# I2C-7313-cTc.net
KiCad netlist of a schematic drawn in EAGLE
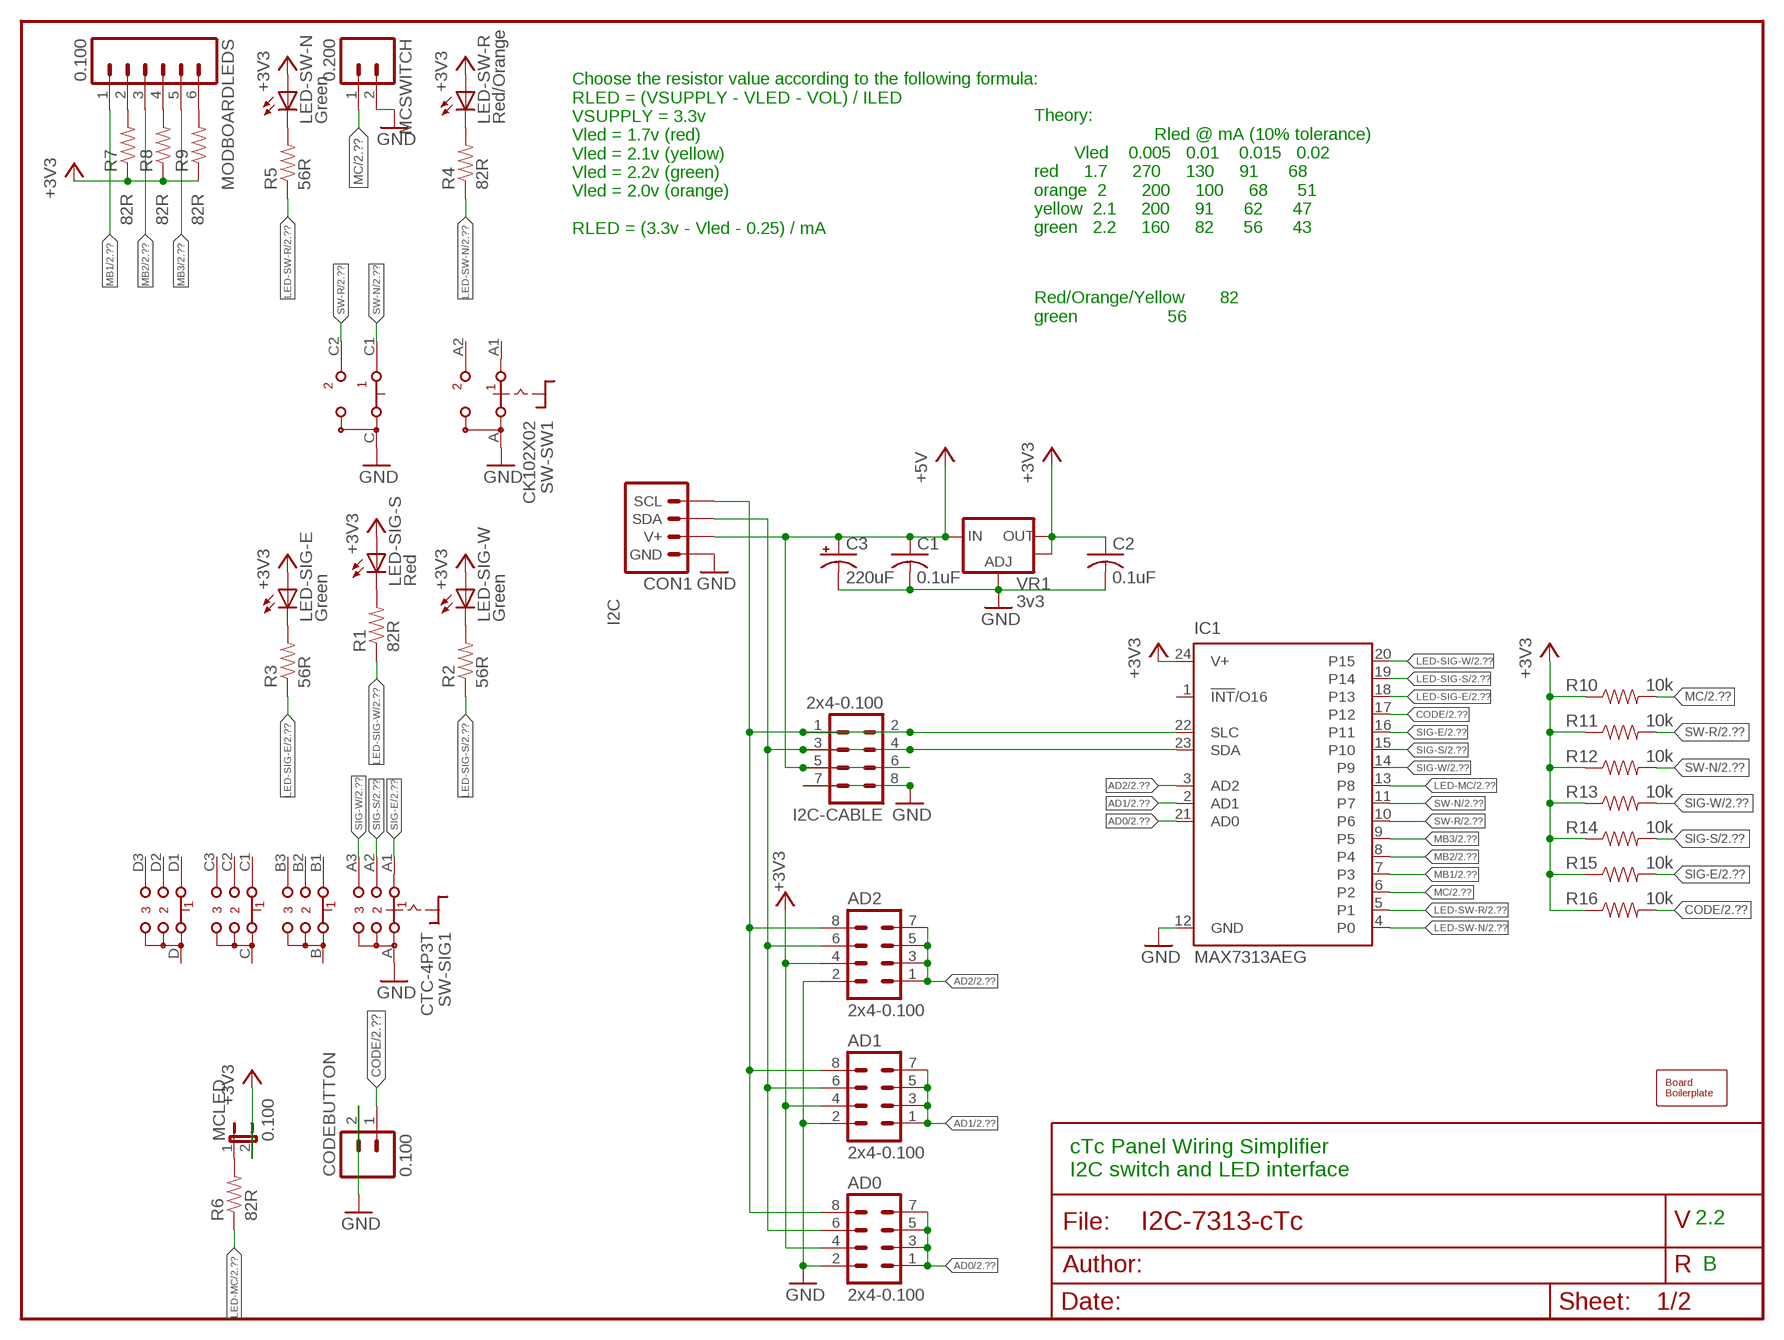
[diagram p0: schematic, sheet 1]
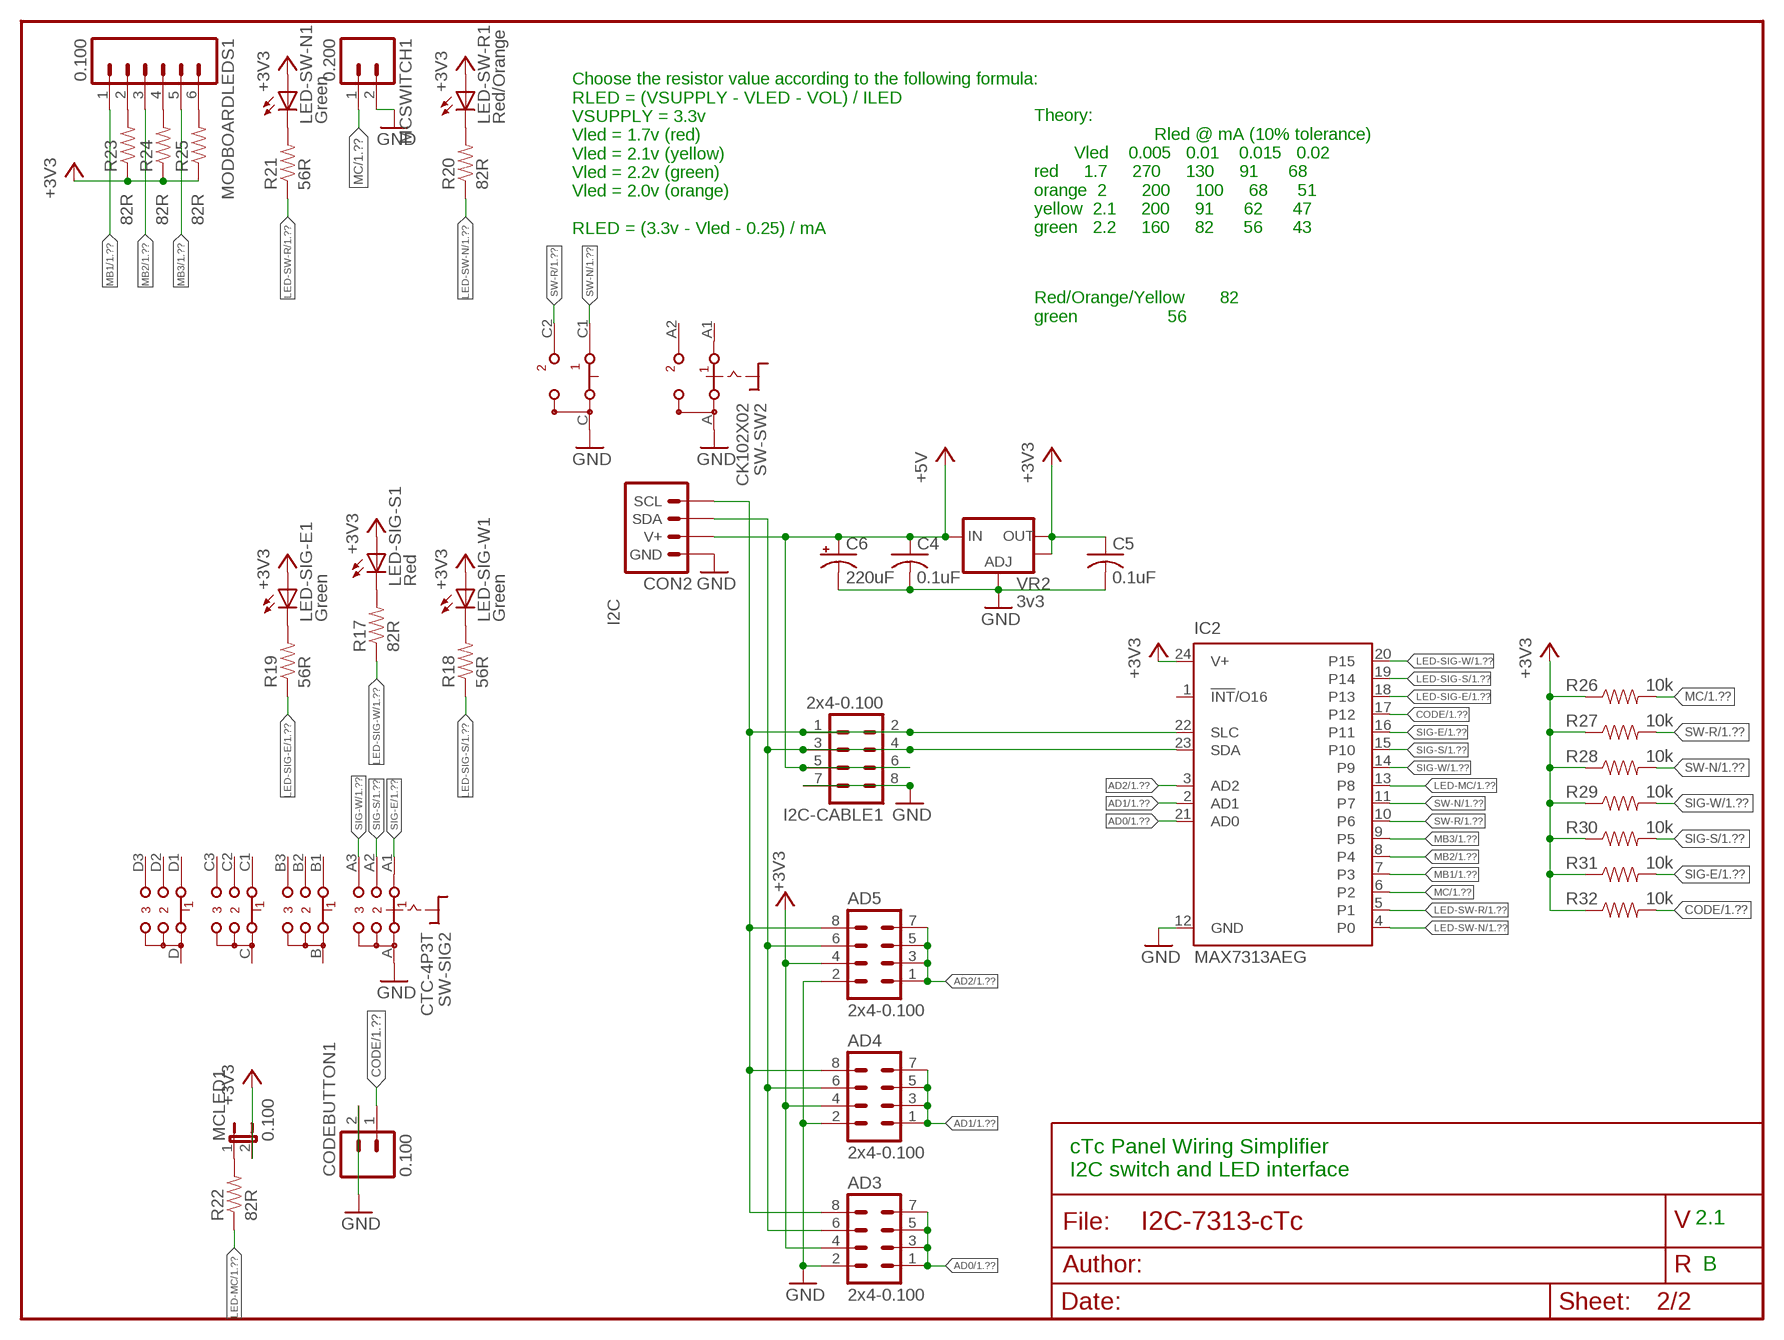
[diagram p1: schematic, sheet 2]

(export (version "E")
  (design (tool "Eeschema 10.0.6"))
  (components
    (comp (ref "AD3")
      (value "2x4-0.100")
      (footprint "eagle-import:MA04-2")
      (libsource (lib "eagle-import") (part "MA04-2"))
    )
    (comp (ref "AD4")
      (value "2x4-0.100")
      (footprint "eagle-import:MA04-2")
      (libsource (lib "eagle-import") (part "MA04-2"))
    )
    (comp (ref "AD5")
      (value "2x4-0.100")
      (footprint "eagle-import:MA04-2")
      (libsource (lib "eagle-import") (part "MA04-2"))
    )
    (comp (ref "C4")
      (value "0.1uF")
      (footprint "eagle-import:0603-CAP")
      (libsource (lib "eagle-import") (part "CAP0603"))
    )
    (comp (ref "C5")
      (value "0.1uF")
      (footprint "eagle-import:0603-CAP")
      (libsource (lib "eagle-import") (part "CAP0603"))
    )
    (comp (ref "C6")
      (value "220uF")
      (footprint "eagle-import:0810-CAP")
      (libsource (lib "eagle-import") (part "CAP-POL0810"))
    )
    (comp (ref "CODEBUTTON1")
      (value "0.100")
      (footprint "eagle-import:1X02_LOCK")
      (libsource (lib "eagle-import") (part "CONNECTOR-M021X02-LOCK"))
    )
    (comp (ref "CON2")
      (value "I2C")
      (footprint "eagle-import:I2C-L")
      (libsource (lib "eagle-import") (part "CONNECTOR-I2CLEFT"))
    )
    (comp (ref "I2C-CABLE1")
      (value "2x4-0.100")
      (footprint "eagle-import:MA04-2")
      (libsource (lib "eagle-import") (part "MA04-2"))
    )
    (comp (ref "IC2")
      (value "MAX7313AEG")
      (footprint "eagle-import:QSOP24")
      (fields (field (name "MPN") "MAX7313AEG+"))
      (libsource (lib "eagle-import") (part "MAX7313AEG"))
    )
    (comp (ref "LED-SIG-E1")
      (value "Green")
      (footprint "eagle-import:LED3MM")
      (libsource (lib "eagle-import") (part "LEDLED3MM"))
    )
    (comp (ref "LED-SIG-S1")
      (value "Red")
      (footprint "eagle-import:LED3MM")
      (libsource (lib "eagle-import") (part "LEDLED3MM"))
    )
    (comp (ref "LED-SIG-W1")
      (value "Green")
      (footprint "eagle-import:LED3MM")
      (libsource (lib "eagle-import") (part "LEDLED3MM"))
    )
    (comp (ref "LED-SW-N1")
      (value "Green")
      (footprint "eagle-import:LED3MM")
      (libsource (lib "eagle-import") (part "LEDLED3MM"))
    )
    (comp (ref "LED-SW-R1")
      (value "Red/Orange")
      (footprint "eagle-import:LED3MM")
      (libsource (lib "eagle-import") (part "LEDLED3MM"))
    )
    (comp (ref "MCLED1")
      (value "0.100")
      (footprint "eagle-import:1X02_LOCK")
      (libsource (lib "eagle-import") (part "JUMPER-2PTH_LOCK"))
    )
    (comp (ref "MCSWITCH1")
      (value "0.200")
      (footprint "eagle-import:SCREWTERMINAL-5MM-2")
      (libsource (lib "eagle-import") (part "CONNECTOR-M025MM-LOCK"))
    )
    (comp (ref "MODBOARDLEDS1")
      (value "0.100")
      (footprint "eagle-import:1X06_LOCK_LONGPADS")
      (libsource (lib "eagle-import") (part "CONNECTOR-M06LOCK_LONGPADS"))
    )
    (comp (ref "R17")
      (value "82R")
      (footprint "eagle-import:0603-RES")
      (libsource (lib "eagle-import") (part "R0603-RES"))
    )
    (comp (ref "R18")
      (value "56R")
      (footprint "eagle-import:0603-RES")
      (libsource (lib "eagle-import") (part "R0603-RES"))
    )
    (comp (ref "R19")
      (value "56R")
      (footprint "eagle-import:0603-RES")
      (libsource (lib "eagle-import") (part "R0603-RES"))
    )
    (comp (ref "R20")
      (value "82R")
      (footprint "eagle-import:0603-RES")
      (libsource (lib "eagle-import") (part "R0603-RES"))
    )
    (comp (ref "R21")
      (value "56R")
      (footprint "eagle-import:0603-RES")
      (libsource (lib "eagle-import") (part "R0603-RES"))
    )
    (comp (ref "R22")
      (value "82R")
      (footprint "eagle-import:0603-RES")
      (libsource (lib "eagle-import") (part "R0603-RES"))
    )
    (comp (ref "R23")
      (value "82R")
      (footprint "eagle-import:0603-RES")
      (libsource (lib "eagle-import") (part "R0603-RES"))
    )
    (comp (ref "R24")
      (value "82R")
      (footprint "eagle-import:0603-RES")
      (libsource (lib "eagle-import") (part "R0603-RES"))
    )
    (comp (ref "R25")
      (value "82R")
      (footprint "eagle-import:0603-RES")
      (libsource (lib "eagle-import") (part "R0603-RES"))
    )
    (comp (ref "R26")
      (value "10k")
      (footprint "eagle-import:0603-RES")
      (libsource (lib "eagle-import") (part "R0603-RES"))
    )
    (comp (ref "R27")
      (value "10k")
      (footprint "eagle-import:0603-RES")
      (libsource (lib "eagle-import") (part "R0603-RES"))
    )
    (comp (ref "R28")
      (value "10k")
      (footprint "eagle-import:0603-RES")
      (libsource (lib "eagle-import") (part "R0603-RES"))
    )
    (comp (ref "R29")
      (value "10k")
      (footprint "eagle-import:0603-RES")
      (libsource (lib "eagle-import") (part "R0603-RES"))
    )
    (comp (ref "R30")
      (value "10k")
      (footprint "eagle-import:0603-RES")
      (libsource (lib "eagle-import") (part "R0603-RES"))
    )
    (comp (ref "R31")
      (value "10k")
      (footprint "eagle-import:0603-RES")
      (libsource (lib "eagle-import") (part "R0603-RES"))
    )
    (comp (ref "R32")
      (value "10k")
      (footprint "eagle-import:0603-RES")
      (libsource (lib "eagle-import") (part "R0603-RES"))
    )
    (comp (ref "SW-SIG2")
      (value "CTC-4P3T")
      (footprint "eagle-import:CTC-4P3T")
      (libsource (lib "eagle-import") (part "CTC-4P3T"))
    )
    (comp (ref "SW-SW2")
      (value "CK102X02")
      (footprint "eagle-import:CK102X02")
      (libsource (lib "eagle-import") (part "CK102X02"))
    )
    (comp (ref "VR2")
      (value "3v3")
      (footprint "eagle-import:SOT223")
      (libsource (lib "eagle-import") (part "VREG_LM1117SOT223"))
    )
    (comp (ref "AD0")
      (value "2x4-0.100")
      (footprint "eagle-import:MA04-2")
      (libsource (lib "eagle-import") (part "MA04-2"))
    )
    (comp (ref "AD1")
      (value "2x4-0.100")
      (footprint "eagle-import:MA04-2")
      (libsource (lib "eagle-import") (part "MA04-2"))
    )
    (comp (ref "AD2")
      (value "2x4-0.100")
      (footprint "eagle-import:MA04-2")
      (libsource (lib "eagle-import") (part "MA04-2"))
    )
    (comp (ref "BOARD1")
      (value "BOARD")
      (footprint "eagle-import:BOARD-SEEED10X15_2-NOHOLES")
      (libsource (lib "eagle-import") (part "BOARD100X150X2-NOHOLES"))
    )
    (comp (ref "C1")
      (value "0.1uF")
      (footprint "eagle-import:0603-CAP")
      (libsource (lib "eagle-import") (part "CAP0603"))
    )
    (comp (ref "C2")
      (value "0.1uF")
      (footprint "eagle-import:0603-CAP")
      (libsource (lib "eagle-import") (part "CAP0603"))
    )
    (comp (ref "C3")
      (value "220uF")
      (footprint "eagle-import:0810-CAP")
      (libsource (lib "eagle-import") (part "CAP-POL0810"))
    )
    (comp (ref "CODEBUTTON")
      (value "0.100")
      (footprint "eagle-import:1X02_LOCK")
      (libsource (lib "eagle-import") (part "CONNECTOR-M021X02-LOCK"))
    )
    (comp (ref "CON1")
      (value "I2C")
      (footprint "eagle-import:I2C-L")
      (libsource (lib "eagle-import") (part "CONNECTOR-I2CLEFT"))
    )
    (comp (ref "I2C-CABLE")
      (value "2x4-0.100")
      (footprint "eagle-import:MA04-2")
      (libsource (lib "eagle-import") (part "MA04-2"))
    )
    (comp (ref "IC1")
      (value "MAX7313AEG")
      (footprint "eagle-import:QSOP24")
      (fields (field (name "MPN") "MAX7313AEG+"))
      (libsource (lib "eagle-import") (part "MAX7313AEG"))
    )
    (comp (ref "LED-SIG-E")
      (value "Green")
      (footprint "eagle-import:LED3MM")
      (libsource (lib "eagle-import") (part "LEDLED3MM"))
    )
    (comp (ref "LED-SIG-S")
      (value "Red")
      (footprint "eagle-import:LED3MM")
      (libsource (lib "eagle-import") (part "LEDLED3MM"))
    )
    (comp (ref "LED-SIG-W")
      (value "Green")
      (footprint "eagle-import:LED3MM")
      (libsource (lib "eagle-import") (part "LEDLED3MM"))
    )
    (comp (ref "LED-SW-N")
      (value "Green")
      (footprint "eagle-import:LED3MM")
      (libsource (lib "eagle-import") (part "LEDLED3MM"))
    )
    (comp (ref "LED-SW-R")
      (value "Red/Orange")
      (footprint "eagle-import:LED3MM")
      (libsource (lib "eagle-import") (part "LEDLED3MM"))
    )
    (comp (ref "MCLED")
      (value "0.100")
      (footprint "eagle-import:1X02_LOCK")
      (libsource (lib "eagle-import") (part "JUMPER-2PTH_LOCK"))
    )
    (comp (ref "MCSWITCH")
      (value "0.200")
      (footprint "eagle-import:SCREWTERMINAL-5MM-2")
      (libsource (lib "eagle-import") (part "CONNECTOR-M025MM-LOCK"))
    )
    (comp (ref "MODBOARDLEDS")
      (value "0.100")
      (footprint "eagle-import:1X06_LOCK_LONGPADS")
      (libsource (lib "eagle-import") (part "CONNECTOR-M06LOCK_LONGPADS"))
    )
    (comp (ref "R1")
      (value "82R")
      (footprint "eagle-import:0603-RES")
      (libsource (lib "eagle-import") (part "R0603-RES"))
    )
    (comp (ref "R2")
      (value "56R")
      (footprint "eagle-import:0603-RES")
      (libsource (lib "eagle-import") (part "R0603-RES"))
    )
    (comp (ref "R3")
      (value "56R")
      (footprint "eagle-import:0603-RES")
      (libsource (lib "eagle-import") (part "R0603-RES"))
    )
    (comp (ref "R4")
      (value "82R")
      (footprint "eagle-import:0603-RES")
      (libsource (lib "eagle-import") (part "R0603-RES"))
    )
    (comp (ref "R5")
      (value "56R")
      (footprint "eagle-import:0603-RES")
      (libsource (lib "eagle-import") (part "R0603-RES"))
    )
    (comp (ref "R6")
      (value "82R")
      (footprint "eagle-import:0603-RES")
      (libsource (lib "eagle-import") (part "R0603-RES"))
    )
    (comp (ref "R7")
      (value "82R")
      (footprint "eagle-import:0603-RES")
      (libsource (lib "eagle-import") (part "R0603-RES"))
    )
    (comp (ref "R8")
      (value "82R")
      (footprint "eagle-import:0603-RES")
      (libsource (lib "eagle-import") (part "R0603-RES"))
    )
    (comp (ref "R9")
      (value "82R")
      (footprint "eagle-import:0603-RES")
      (libsource (lib "eagle-import") (part "R0603-RES"))
    )
    (comp (ref "R10")
      (value "10k")
      (footprint "eagle-import:0603-RES")
      (libsource (lib "eagle-import") (part "R0603-RES"))
    )
    (comp (ref "R11")
      (value "10k")
      (footprint "eagle-import:0603-RES")
      (libsource (lib "eagle-import") (part "R0603-RES"))
    )
    (comp (ref "R12")
      (value "10k")
      (footprint "eagle-import:0603-RES")
      (libsource (lib "eagle-import") (part "R0603-RES"))
    )
    (comp (ref "R13")
      (value "10k")
      (footprint "eagle-import:0603-RES")
      (libsource (lib "eagle-import") (part "R0603-RES"))
    )
    (comp (ref "R14")
      (value "10k")
      (footprint "eagle-import:0603-RES")
      (libsource (lib "eagle-import") (part "R0603-RES"))
    )
    (comp (ref "R15")
      (value "10k")
      (footprint "eagle-import:0603-RES")
      (libsource (lib "eagle-import") (part "R0603-RES"))
    )
    (comp (ref "R16")
      (value "10k")
      (footprint "eagle-import:0603-RES")
      (libsource (lib "eagle-import") (part "R0603-RES"))
    )
    (comp (ref "SW-SIG1")
      (value "CTC-4P3T")
      (footprint "eagle-import:CTC-4P3T")
      (libsource (lib "eagle-import") (part "CTC-4P3T"))
    )
    (comp (ref "SW-SW1")
      (value "CK102X02")
      (footprint "eagle-import:CK102X02")
      (libsource (lib "eagle-import") (part "CK102X02"))
    )
    (comp (ref "VR1")
      (value "3v3")
      (footprint "eagle-import:SOT223")
      (libsource (lib "eagle-import") (part "VREG_LM1117SOT223"))
    )
  )
  (nets
    (net (code "1") (name "+3V3") (class "Default")
      (node (ref "AD0") (pin "4") (pinfunction "4_4") (pintype "passive"))
      (node (ref "AD1") (pin "4") (pinfunction "4_4") (pintype "passive"))
      (node (ref "AD2") (pin "4") (pinfunction "4_4") (pintype "passive"))
      (node (ref "AD3") (pin "4") (pinfunction "4_4") (pintype "passive"))
      (node (ref "AD4") (pin "4") (pinfunction "4_4") (pintype "passive"))
      (node (ref "AD5") (pin "4") (pinfunction "4_4") (pintype "passive"))
      (node (ref "C2") (pin "1") (pinfunction "1_1") (pintype "passive"))
      (node (ref "C5") (pin "1") (pinfunction "1_1") (pintype "passive"))
      (node (ref "IC1") (pin "24") (pinfunction "V+_24") (pintype "power_in"))
      (node (ref "IC2") (pin "24") (pinfunction "V+_24") (pintype "power_in"))
      (node (ref "LED-SIG-E") (pin "A") (pinfunction "A_A") (pintype "passive"))
      (node (ref "LED-SIG-E1") (pin "A") (pinfunction "A_A") (pintype "passive"))
      (node (ref "LED-SIG-S") (pin "A") (pinfunction "A_A") (pintype "passive"))
      (node (ref "LED-SIG-S1") (pin "A") (pinfunction "A_A") (pintype "passive"))
      (node (ref "LED-SIG-W") (pin "A") (pinfunction "A_A") (pintype "passive"))
      (node (ref "LED-SIG-W1") (pin "A") (pinfunction "A_A") (pintype "passive"))
      (node (ref "LED-SW-N") (pin "A") (pinfunction "A_A") (pintype "passive"))
      (node (ref "LED-SW-N1") (pin "A") (pinfunction "A_A") (pintype "passive"))
      (node (ref "LED-SW-R") (pin "A") (pinfunction "A_A") (pintype "passive"))
      (node (ref "LED-SW-R1") (pin "A") (pinfunction "A_A") (pintype "passive"))
      (node (ref "MCLED") (pin "2") (pinfunction "2_2") (pintype "passive"))
      (node (ref "MCLED1") (pin "2") (pinfunction "2_2") (pintype "passive"))
      (node (ref "R10") (pin "1") (pinfunction "1_1") (pintype "passive"))
      (node (ref "R11") (pin "1") (pinfunction "1_1") (pintype "passive"))
      (node (ref "R12") (pin "1") (pinfunction "1_1") (pintype "passive"))
      (node (ref "R13") (pin "1") (pinfunction "1_1") (pintype "passive"))
      (node (ref "R14") (pin "1") (pinfunction "1_1") (pintype "passive"))
      (node (ref "R15") (pin "1") (pinfunction "1_1") (pintype "passive"))
      (node (ref "R16") (pin "1") (pinfunction "1_1") (pintype "passive"))
      (node (ref "R23") (pin "1") (pinfunction "1_1") (pintype "passive"))
      (node (ref "R24") (pin "1") (pinfunction "1_1") (pintype "passive"))
      (node (ref "R25") (pin "1") (pinfunction "1_1") (pintype "passive"))
      (node (ref "R26") (pin "1") (pinfunction "1_1") (pintype "passive"))
      (node (ref "R27") (pin "1") (pinfunction "1_1") (pintype "passive"))
      (node (ref "R28") (pin "1") (pinfunction "1_1") (pintype "passive"))
      (node (ref "R29") (pin "1") (pinfunction "1_1") (pintype "passive"))
      (node (ref "R30") (pin "1") (pinfunction "1_1") (pintype "passive"))
      (node (ref "R31") (pin "1") (pinfunction "1_1") (pintype "passive"))
      (node (ref "R32") (pin "1") (pinfunction "1_1") (pintype "passive"))
      (node (ref "R7") (pin "1") (pinfunction "1_1") (pintype "passive"))
      (node (ref "R8") (pin "1") (pinfunction "1_1") (pintype "passive"))
      (node (ref "R9") (pin "1") (pinfunction "1_1") (pintype "passive"))
      (node (ref "VR1") (pin "2") (pinfunction "OUT_2") (pintype "power_in"))
      (node (ref "VR1") (pin "4") (pinfunction "OUT_4") (pintype "power_in"))
      (node (ref "VR2") (pin "2") (pinfunction "OUT_2") (pintype "power_in"))
      (node (ref "VR2") (pin "4") (pinfunction "OUT_4") (pintype "power_in"))
    )
    (net (code "2") (name "+5V") (class "Default")
      (node (ref "C1") (pin "1") (pinfunction "1_1") (pintype "passive"))
      (node (ref "C3") (pin "+") (pinfunction "+_+") (pintype "passive"))
      (node (ref "C4") (pin "1") (pinfunction "1_1") (pintype "passive"))
      (node (ref "C6") (pin "+") (pinfunction "+_+") (pintype "passive"))
      (node (ref "CON1") (pin "V+") (pinfunction "V+_V+") (pintype "passive"))
      (node (ref "CON1") (pin "V+@1") (pinfunction "V+_V+@1") (pintype "passive"))
      (node (ref "CON2") (pin "V+") (pinfunction "V+_V+") (pintype "passive"))
      (node (ref "CON2") (pin "V+@1") (pinfunction "V+_V+@1") (pintype "passive"))
      (node (ref "I2C-CABLE") (pin "5") (pinfunction "5_5") (pintype "passive"))
      (node (ref "I2C-CABLE") (pin "6") (pinfunction "6_6") (pintype "passive"))
      (node (ref "I2C-CABLE1") (pin "5") (pinfunction "5_5") (pintype "passive"))
      (node (ref "I2C-CABLE1") (pin "6") (pinfunction "6_6") (pintype "passive"))
      (node (ref "VR1") (pin "3") (pinfunction "IN_3") (pintype "input"))
      (node (ref "VR2") (pin "3") (pinfunction "IN_3") (pintype "input"))
    )
    (net (code "3") (name "AD0") (class "Default")
      (node (ref "AD0") (pin "1") (pinfunction "1_1") (pintype "passive"))
      (node (ref "AD0") (pin "3") (pinfunction "3_3") (pintype "passive"))
      (node (ref "AD0") (pin "5") (pinfunction "5_5") (pintype "passive"))
      (node (ref "AD0") (pin "7") (pinfunction "7_7") (pintype "passive"))
      (node (ref "AD3") (pin "1") (pinfunction "1_1") (pintype "passive"))
      (node (ref "AD3") (pin "3") (pinfunction "3_3") (pintype "passive"))
      (node (ref "AD3") (pin "5") (pinfunction "5_5") (pintype "passive"))
      (node (ref "AD3") (pin "7") (pinfunction "7_7") (pintype "passive"))
      (node (ref "IC1") (pin "21") (pinfunction "AD0_21") (pintype "input"))
      (node (ref "IC2") (pin "21") (pinfunction "AD0_21") (pintype "input"))
    )
    (net (code "4") (name "AD1") (class "Default")
      (node (ref "AD1") (pin "1") (pinfunction "1_1") (pintype "passive"))
      (node (ref "AD1") (pin "3") (pinfunction "3_3") (pintype "passive"))
      (node (ref "AD1") (pin "5") (pinfunction "5_5") (pintype "passive"))
      (node (ref "AD1") (pin "7") (pinfunction "7_7") (pintype "passive"))
      (node (ref "AD4") (pin "1") (pinfunction "1_1") (pintype "passive"))
      (node (ref "AD4") (pin "3") (pinfunction "3_3") (pintype "passive"))
      (node (ref "AD4") (pin "5") (pinfunction "5_5") (pintype "passive"))
      (node (ref "AD4") (pin "7") (pinfunction "7_7") (pintype "passive"))
      (node (ref "IC1") (pin "2") (pinfunction "AD1_2") (pintype "input"))
      (node (ref "IC2") (pin "2") (pinfunction "AD1_2") (pintype "input"))
    )
    (net (code "5") (name "AD2") (class "Default")
      (node (ref "AD2") (pin "1") (pinfunction "1_1") (pintype "passive"))
      (node (ref "AD2") (pin "3") (pinfunction "3_3") (pintype "passive"))
      (node (ref "AD2") (pin "5") (pinfunction "5_5") (pintype "passive"))
      (node (ref "AD2") (pin "7") (pinfunction "7_7") (pintype "passive"))
      (node (ref "AD5") (pin "1") (pinfunction "1_1") (pintype "passive"))
      (node (ref "AD5") (pin "3") (pinfunction "3_3") (pintype "passive"))
      (node (ref "AD5") (pin "5") (pinfunction "5_5") (pintype "passive"))
      (node (ref "AD5") (pin "7") (pinfunction "7_7") (pintype "passive"))
      (node (ref "IC1") (pin "3") (pinfunction "AD2_3") (pintype "input"))
      (node (ref "IC2") (pin "3") (pinfunction "AD2_3") (pintype "input"))
    )
    (net (code "6") (name "CODE") (class "Default")
      (node (ref "CODEBUTTON") (pin "1") (pinfunction "A_1") (pintype "passive"))
      (node (ref "CODEBUTTON1") (pin "1") (pinfunction "A_1") (pintype "passive"))
      (node (ref "IC1") (pin "17") (pinfunction "P12_17") (pintype "bidirectional"))
      (node (ref "IC2") (pin "17") (pinfunction "P12_17") (pintype "bidirectional"))
      (node (ref "R16") (pin "2") (pinfunction "2_2") (pintype "passive"))
      (node (ref "R32") (pin "2") (pinfunction "2_2") (pintype "passive"))
    )
    (net (code "7") (name "GND") (class "Default")
      (node (ref "AD0") (pin "2") (pinfunction "2_2") (pintype "passive"))
      (node (ref "AD1") (pin "2") (pinfunction "2_2") (pintype "passive"))
      (node (ref "AD2") (pin "2") (pinfunction "2_2") (pintype "passive"))
      (node (ref "AD3") (pin "2") (pinfunction "2_2") (pintype "passive"))
      (node (ref "AD4") (pin "2") (pinfunction "2_2") (pintype "passive"))
      (node (ref "AD5") (pin "2") (pinfunction "2_2") (pintype "passive"))
      (node (ref "C1") (pin "2") (pinfunction "2_2") (pintype "passive"))
      (node (ref "C2") (pin "2") (pinfunction "2_2") (pintype "passive"))
      (node (ref "C3") (pin "-") (pinfunction "-_-") (pintype "passive"))
      (node (ref "C4") (pin "2") (pinfunction "2_2") (pintype "passive"))
      (node (ref "C5") (pin "2") (pinfunction "2_2") (pintype "passive"))
      (node (ref "C6") (pin "-") (pinfunction "-_-") (pintype "passive"))
      (node (ref "CODEBUTTON") (pin "2") (pinfunction "B_2") (pintype "passive"))
      (node (ref "CODEBUTTON1") (pin "2") (pinfunction "B_2") (pintype "passive"))
      (node (ref "CON1") (pin "GND") (pinfunction "GND_GND") (pintype "passive"))
      (node (ref "CON1") (pin "GND@1") (pinfunction "GND_GND@1") (pintype "passive"))
      (node (ref "CON2") (pin "GND") (pinfunction "GND_GND") (pintype "passive"))
      (node (ref "CON2") (pin "GND@1") (pinfunction "GND_GND@1") (pintype "passive"))
      (node (ref "I2C-CABLE") (pin "7") (pinfunction "7_7") (pintype "passive"))
      (node (ref "I2C-CABLE") (pin "8") (pinfunction "8_8") (pintype "passive"))
      (node (ref "I2C-CABLE1") (pin "7") (pinfunction "7_7") (pintype "passive"))
      (node (ref "I2C-CABLE1") (pin "8") (pinfunction "8_8") (pintype "passive"))
      (node (ref "IC1") (pin "12") (pinfunction "GND_12") (pintype "power_in"))
      (node (ref "IC2") (pin "12") (pinfunction "GND_12") (pintype "power_in"))
      (node (ref "MCSWITCH") (pin "2") (pinfunction "B_2") (pintype "passive"))
      (node (ref "MCSWITCH1") (pin "2") (pinfunction "B_2") (pintype "passive"))
      (node (ref "SW-SIG1") (pin "A") (pinfunction "A_A") (pintype "passive"))
      (node (ref "SW-SIG2") (pin "A") (pinfunction "A_A") (pintype "passive"))
      (node (ref "SW-SW1") (pin "A") (pinfunction "A_A") (pintype "passive"))
      (node (ref "SW-SW1") (pin "C") (pinfunction "C_C") (pintype "passive"))
      (node (ref "SW-SW2") (pin "A") (pinfunction "A_A") (pintype "passive"))
      (node (ref "SW-SW2") (pin "C") (pinfunction "C_C") (pintype "passive"))
      (node (ref "VR1") (pin "1") (pinfunction "ADJ_1") (pintype "input"))
      (node (ref "VR2") (pin "1") (pinfunction "ADJ_1") (pintype "input"))
    )
    (net (code "8") (name "LED-MC") (class "Default")
      (node (ref "IC1") (pin "13") (pinfunction "P8_13") (pintype "bidirectional"))
      (node (ref "IC2") (pin "13") (pinfunction "P8_13") (pintype "bidirectional"))
      (node (ref "R22") (pin "1") (pinfunction "1_1") (pintype "passive"))
      (node (ref "R6") (pin "1") (pinfunction "1_1") (pintype "passive"))
    )
    (net (code "9") (name "LED-SIG-E") (class "Default")
      (node (ref "IC1") (pin "18") (pinfunction "P13_18") (pintype "bidirectional"))
      (node (ref "IC2") (pin "18") (pinfunction "P13_18") (pintype "bidirectional"))
      (node (ref "R19") (pin "1") (pinfunction "1_1") (pintype "passive"))
      (node (ref "R3") (pin "1") (pinfunction "1_1") (pintype "passive"))
    )
    (net (code "10") (name "LED-SIG-S") (class "Default")
      (node (ref "IC1") (pin "19") (pinfunction "P14_19") (pintype "bidirectional"))
      (node (ref "IC2") (pin "19") (pinfunction "P14_19") (pintype "bidirectional"))
      (node (ref "R18") (pin "1") (pinfunction "1_1") (pintype "passive"))
      (node (ref "R2") (pin "1") (pinfunction "1_1") (pintype "passive"))
    )
    (net (code "11") (name "LED-SIG-W") (class "Default")
      (node (ref "IC1") (pin "20") (pinfunction "P15_20") (pintype "bidirectional"))
      (node (ref "IC2") (pin "20") (pinfunction "P15_20") (pintype "bidirectional"))
      (node (ref "R1") (pin "1") (pinfunction "1_1") (pintype "passive"))
      (node (ref "R17") (pin "1") (pinfunction "1_1") (pintype "passive"))
    )
    (net (code "12") (name "LED-SW-N") (class "Default")
      (node (ref "IC1") (pin "4") (pinfunction "P0_4") (pintype "bidirectional"))
      (node (ref "IC2") (pin "4") (pinfunction "P0_4") (pintype "bidirectional"))
      (node (ref "R20") (pin "1") (pinfunction "1_1") (pintype "passive"))
      (node (ref "R4") (pin "1") (pinfunction "1_1") (pintype "passive"))
    )
    (net (code "13") (name "LED-SW-R") (class "Default")
      (node (ref "IC1") (pin "5") (pinfunction "P1_5") (pintype "bidirectional"))
      (node (ref "IC2") (pin "5") (pinfunction "P1_5") (pintype "bidirectional"))
      (node (ref "R21") (pin "1") (pinfunction "1_1") (pintype "passive"))
      (node (ref "R5") (pin "1") (pinfunction "1_1") (pintype "passive"))
    )
    (net (code "14") (name "MB1") (class "Default")
      (node (ref "IC1") (pin "7") (pinfunction "P3_7") (pintype "bidirectional"))
      (node (ref "IC2") (pin "7") (pinfunction "P3_7") (pintype "bidirectional"))
      (node (ref "MODBOARDLEDS") (pin "1") (pinfunction "1_1") (pintype "passive"))
      (node (ref "MODBOARDLEDS1") (pin "1") (pinfunction "1_1") (pintype "passive"))
    )
    (net (code "15") (name "MB2") (class "Default")
      (node (ref "IC1") (pin "8") (pinfunction "P4_8") (pintype "bidirectional"))
      (node (ref "IC2") (pin "8") (pinfunction "P4_8") (pintype "bidirectional"))
      (node (ref "MODBOARDLEDS") (pin "3") (pinfunction "3_3") (pintype "passive"))
      (node (ref "MODBOARDLEDS1") (pin "3") (pinfunction "3_3") (pintype "passive"))
    )
    (net (code "16") (name "MB3") (class "Default")
      (node (ref "IC1") (pin "9") (pinfunction "P5_9") (pintype "bidirectional"))
      (node (ref "IC2") (pin "9") (pinfunction "P5_9") (pintype "bidirectional"))
      (node (ref "MODBOARDLEDS") (pin "5") (pinfunction "5_5") (pintype "passive"))
      (node (ref "MODBOARDLEDS1") (pin "5") (pinfunction "5_5") (pintype "passive"))
    )
    (net (code "17") (name "MC") (class "Default")
      (node (ref "IC1") (pin "6") (pinfunction "P2_6") (pintype "bidirectional"))
      (node (ref "IC2") (pin "6") (pinfunction "P2_6") (pintype "bidirectional"))
      (node (ref "MCSWITCH") (pin "1") (pinfunction "A_1") (pintype "passive"))
      (node (ref "MCSWITCH1") (pin "1") (pinfunction "A_1") (pintype "passive"))
      (node (ref "R10") (pin "2") (pinfunction "2_2") (pintype "passive"))
      (node (ref "R26") (pin "2") (pinfunction "2_2") (pintype "passive"))
    )
    (net (code "18") (name "Net-(IC1-SDA)") (class "Default")
      (node (ref "AD0") (pin "6") (pinfunction "6_6") (pintype "passive"))
      (node (ref "AD1") (pin "6") (pinfunction "6_6") (pintype "passive"))
      (node (ref "AD2") (pin "6") (pinfunction "6_6") (pintype "passive"))
      (node (ref "CON1") (pin "SDA") (pinfunction "SDA_SDA") (pintype "passive"))
      (node (ref "CON1") (pin "SDA@1") (pinfunction "SDA_SDA@1") (pintype "passive"))
      (node (ref "I2C-CABLE") (pin "3") (pinfunction "3_3") (pintype "passive"))
      (node (ref "I2C-CABLE") (pin "4") (pinfunction "4_4") (pintype "passive"))
      (node (ref "IC1") (pin "23") (pinfunction "SDA_23") (pintype "bidirectional"))
    )
    (net (code "19") (name "Net-(IC1-SLC)") (class "Default")
      (node (ref "AD0") (pin "8") (pinfunction "8_8") (pintype "passive"))
      (node (ref "AD1") (pin "8") (pinfunction "8_8") (pintype "passive"))
      (node (ref "AD2") (pin "8") (pinfunction "8_8") (pintype "passive"))
      (node (ref "CON1") (pin "SCL") (pinfunction "SCL_SCL") (pintype "passive"))
      (node (ref "CON1") (pin "SCL@1") (pinfunction "SCL_SCL@1") (pintype "passive"))
      (node (ref "I2C-CABLE") (pin "1") (pinfunction "1_1") (pintype "passive"))
      (node (ref "I2C-CABLE") (pin "2") (pinfunction "2_2") (pintype "passive"))
      (node (ref "IC1") (pin "22") (pinfunction "SLC_22") (pintype "input"))
    )
    (net (code "20") (name "Net-(IC2-SDA)") (class "Default")
      (node (ref "AD3") (pin "6") (pinfunction "6_6") (pintype "passive"))
      (node (ref "AD4") (pin "6") (pinfunction "6_6") (pintype "passive"))
      (node (ref "AD5") (pin "6") (pinfunction "6_6") (pintype "passive"))
      (node (ref "CON2") (pin "SDA") (pinfunction "SDA_SDA") (pintype "passive"))
      (node (ref "CON2") (pin "SDA@1") (pinfunction "SDA_SDA@1") (pintype "passive"))
      (node (ref "I2C-CABLE1") (pin "3") (pinfunction "3_3") (pintype "passive"))
      (node (ref "I2C-CABLE1") (pin "4") (pinfunction "4_4") (pintype "passive"))
      (node (ref "IC2") (pin "23") (pinfunction "SDA_23") (pintype "bidirectional"))
    )
    (net (code "21") (name "Net-(IC2-SLC)") (class "Default")
      (node (ref "AD3") (pin "8") (pinfunction "8_8") (pintype "passive"))
      (node (ref "AD4") (pin "8") (pinfunction "8_8") (pintype "passive"))
      (node (ref "AD5") (pin "8") (pinfunction "8_8") (pintype "passive"))
      (node (ref "CON2") (pin "SCL") (pinfunction "SCL_SCL") (pintype "passive"))
      (node (ref "CON2") (pin "SCL@1") (pinfunction "SCL_SCL@1") (pintype "passive"))
      (node (ref "I2C-CABLE1") (pin "1") (pinfunction "1_1") (pintype "passive"))
      (node (ref "I2C-CABLE1") (pin "2") (pinfunction "2_2") (pintype "passive"))
      (node (ref "IC2") (pin "22") (pinfunction "SLC_22") (pintype "input"))
    )
    (net (code "22") (name "Net-(LED-SIG-E-C)") (class "Default")
      (node (ref "LED-SIG-E") (pin "K") (pinfunction "C_K") (pintype "passive"))
      (node (ref "R3") (pin "2") (pinfunction "2_2") (pintype "passive"))
    )
    (net (code "23") (name "Net-(LED-SIG-E1-C)") (class "Default")
      (node (ref "LED-SIG-E1") (pin "K") (pinfunction "C_K") (pintype "passive"))
      (node (ref "R19") (pin "2") (pinfunction "2_2") (pintype "passive"))
    )
    (net (code "24") (name "Net-(LED-SIG-S-C)") (class "Default")
      (node (ref "LED-SIG-S") (pin "K") (pinfunction "C_K") (pintype "passive"))
      (node (ref "R1") (pin "2") (pinfunction "2_2") (pintype "passive"))
    )
    (net (code "25") (name "Net-(LED-SIG-S1-C)") (class "Default")
      (node (ref "LED-SIG-S1") (pin "K") (pinfunction "C_K") (pintype "passive"))
      (node (ref "R17") (pin "2") (pinfunction "2_2") (pintype "passive"))
    )
    (net (code "26") (name "Net-(LED-SIG-W-C)") (class "Default")
      (node (ref "LED-SIG-W") (pin "K") (pinfunction "C_K") (pintype "passive"))
      (node (ref "R2") (pin "2") (pinfunction "2_2") (pintype "passive"))
    )
    (net (code "27") (name "Net-(LED-SIG-W1-C)") (class "Default")
      (node (ref "LED-SIG-W1") (pin "K") (pinfunction "C_K") (pintype "passive"))
      (node (ref "R18") (pin "2") (pinfunction "2_2") (pintype "passive"))
    )
    (net (code "28") (name "Net-(LED-SW-N-C)") (class "Default")
      (node (ref "LED-SW-N") (pin "K") (pinfunction "C_K") (pintype "passive"))
      (node (ref "R5") (pin "2") (pinfunction "2_2") (pintype "passive"))
    )
    (net (code "29") (name "Net-(LED-SW-N1-C)") (class "Default")
      (node (ref "LED-SW-N1") (pin "K") (pinfunction "C_K") (pintype "passive"))
      (node (ref "R21") (pin "2") (pinfunction "2_2") (pintype "passive"))
    )
    (net (code "30") (name "Net-(LED-SW-R-C)") (class "Default")
      (node (ref "LED-SW-R") (pin "K") (pinfunction "C_K") (pintype "passive"))
      (node (ref "R4") (pin "2") (pinfunction "2_2") (pintype "passive"))
    )
    (net (code "31") (name "Net-(LED-SW-R1-C)") (class "Default")
      (node (ref "LED-SW-R1") (pin "K") (pinfunction "C_K") (pintype "passive"))
      (node (ref "R20") (pin "2") (pinfunction "2_2") (pintype "passive"))
    )
    (net (code "32") (name "Net-(MCLED-Pad1)") (class "Default")
      (node (ref "MCLED") (pin "1") (pinfunction "1_1") (pintype "passive"))
      (node (ref "R6") (pin "2") (pinfunction "2_2") (pintype "passive"))
    )
    (net (code "33") (name "Net-(MCLED1-Pad1)") (class "Default")
      (node (ref "MCLED1") (pin "1") (pinfunction "1_1") (pintype "passive"))
      (node (ref "R22") (pin "2") (pinfunction "2_2") (pintype "passive"))
    )
    (net (code "34") (name "Net-(MODBOARDLEDS-Pad2)") (class "Default")
      (node (ref "MODBOARDLEDS") (pin "2") (pinfunction "2_2") (pintype "passive"))
      (node (ref "R7") (pin "2") (pinfunction "2_2") (pintype "passive"))
    )
    (net (code "35") (name "Net-(MODBOARDLEDS-Pad4)") (class "Default")
      (node (ref "MODBOARDLEDS") (pin "4") (pinfunction "4_4") (pintype "passive"))
      (node (ref "R8") (pin "2") (pinfunction "2_2") (pintype "passive"))
    )
    (net (code "36") (name "Net-(MODBOARDLEDS-Pad6)") (class "Default")
      (node (ref "MODBOARDLEDS") (pin "6") (pinfunction "6_6") (pintype "passive"))
      (node (ref "R9") (pin "2") (pinfunction "2_2") (pintype "passive"))
    )
    (net (code "37") (name "Net-(MODBOARDLEDS1-Pad2)") (class "Default")
      (node (ref "MODBOARDLEDS1") (pin "2") (pinfunction "2_2") (pintype "passive"))
      (node (ref "R23") (pin "2") (pinfunction "2_2") (pintype "passive"))
    )
    (net (code "38") (name "Net-(MODBOARDLEDS1-Pad4)") (class "Default")
      (node (ref "MODBOARDLEDS1") (pin "4") (pinfunction "4_4") (pintype "passive"))
      (node (ref "R24") (pin "2") (pinfunction "2_2") (pintype "passive"))
    )
    (net (code "39") (name "Net-(MODBOARDLEDS1-Pad6)") (class "Default")
      (node (ref "MODBOARDLEDS1") (pin "6") (pinfunction "6_6") (pintype "passive"))
      (node (ref "R25") (pin "2") (pinfunction "2_2") (pintype "passive"))
    )
    (net (code "40") (name "SIG-E") (class "Default")
      (node (ref "IC1") (pin "16") (pinfunction "P11_16") (pintype "bidirectional"))
      (node (ref "IC2") (pin "16") (pinfunction "P11_16") (pintype "bidirectional"))
      (node (ref "R15") (pin "2") (pinfunction "2_2") (pintype "passive"))
      (node (ref "R31") (pin "2") (pinfunction "2_2") (pintype "passive"))
      (node (ref "SW-SIG1") (pin "A1") (pinfunction "A1_A1") (pintype "passive"))
      (node (ref "SW-SIG2") (pin "A1") (pinfunction "A1_A1") (pintype "passive"))
    )
    (net (code "41") (name "SIG-S") (class "Default")
      (node (ref "IC1") (pin "15") (pinfunction "P10_15") (pintype "bidirectional"))
      (node (ref "IC2") (pin "15") (pinfunction "P10_15") (pintype "bidirectional"))
      (node (ref "R14") (pin "2") (pinfunction "2_2") (pintype "passive"))
      (node (ref "R30") (pin "2") (pinfunction "2_2") (pintype "passive"))
      (node (ref "SW-SIG1") (pin "A2") (pinfunction "A2_A2") (pintype "passive"))
      (node (ref "SW-SIG2") (pin "A2") (pinfunction "A2_A2") (pintype "passive"))
    )
    (net (code "42") (name "SIG-W") (class "Default")
      (node (ref "IC1") (pin "14") (pinfunction "P9_14") (pintype "bidirectional"))
      (node (ref "IC2") (pin "14") (pinfunction "P9_14") (pintype "bidirectional"))
      (node (ref "R13") (pin "2") (pinfunction "2_2") (pintype "passive"))
      (node (ref "R29") (pin "2") (pinfunction "2_2") (pintype "passive"))
      (node (ref "SW-SIG1") (pin "A3") (pinfunction "A3_A3") (pintype "passive"))
      (node (ref "SW-SIG2") (pin "A3") (pinfunction "A3_A3") (pintype "passive"))
    )
    (net (code "43") (name "SW-N") (class "Default")
      (node (ref "IC1") (pin "11") (pinfunction "P7_11") (pintype "bidirectional"))
      (node (ref "IC2") (pin "11") (pinfunction "P7_11") (pintype "bidirectional"))
      (node (ref "R12") (pin "2") (pinfunction "2_2") (pintype "passive"))
      (node (ref "R28") (pin "2") (pinfunction "2_2") (pintype "passive"))
      (node (ref "SW-SW1") (pin "C1") (pinfunction "C1_C1") (pintype "passive"))
      (node (ref "SW-SW2") (pin "C1") (pinfunction "C1_C1") (pintype "passive"))
    )
    (net (code "44") (name "SW-R") (class "Default")
      (node (ref "IC1") (pin "10") (pinfunction "P6_10") (pintype "bidirectional"))
      (node (ref "IC2") (pin "10") (pinfunction "P6_10") (pintype "bidirectional"))
      (node (ref "R11") (pin "2") (pinfunction "2_2") (pintype "passive"))
      (node (ref "R27") (pin "2") (pinfunction "2_2") (pintype "passive"))
      (node (ref "SW-SW1") (pin "C2") (pinfunction "C2_C2") (pintype "passive"))
      (node (ref "SW-SW2") (pin "C2") (pinfunction "C2_C2") (pintype "passive"))
    )
    (net (code "45") (name "unconnected-(IC1-~{INT}{slash}O16-Pad1)") (class "Default")
      (node (ref "IC1") (pin "1") (pinfunction "~{INT}/O16_1") (pintype "open_collector"))
    )
    (net (code "46") (name "unconnected-(IC2-~{INT}{slash}O16-Pad1)") (class "Default")
      (node (ref "IC2") (pin "1") (pinfunction "~{INT}/O16_1") (pintype "open_collector"))
    )
    (net (code "47") (name "unconnected-(SW-SIG1-PadB)") (class "Default")
      (node (ref "SW-SIG1") (pin "B") (pinfunction "B_B") (pintype "passive"))
    )
    (net (code "48") (name "unconnected-(SW-SIG1-PadB1)") (class "Default")
      (node (ref "SW-SIG1") (pin "B1") (pinfunction "B1_B1") (pintype "passive"))
    )
    (net (code "49") (name "unconnected-(SW-SIG1-PadB2)") (class "Default")
      (node (ref "SW-SIG1") (pin "B2") (pinfunction "B2_B2") (pintype "passive"))
    )
    (net (code "50") (name "unconnected-(SW-SIG1-PadB3)") (class "Default")
      (node (ref "SW-SIG1") (pin "B3") (pinfunction "B3_B3") (pintype "passive"))
    )
    (net (code "51") (name "unconnected-(SW-SIG1-PadC)") (class "Default")
      (node (ref "SW-SIG1") (pin "C") (pinfunction "C_C") (pintype "passive"))
    )
    (net (code "52") (name "unconnected-(SW-SIG1-PadC1)") (class "Default")
      (node (ref "SW-SIG1") (pin "C1") (pinfunction "C1_C1") (pintype "passive"))
    )
    (net (code "53") (name "unconnected-(SW-SIG1-PadC2)") (class "Default")
      (node (ref "SW-SIG1") (pin "C2") (pinfunction "C2_C2") (pintype "passive"))
    )
    (net (code "54") (name "unconnected-(SW-SIG1-PadC3)") (class "Default")
      (node (ref "SW-SIG1") (pin "C3") (pinfunction "C3_C3") (pintype "passive"))
    )
    (net (code "55") (name "unconnected-(SW-SIG1-PadD)") (class "Default")
      (node (ref "SW-SIG1") (pin "D") (pinfunction "D_D") (pintype "passive"))
    )
    (net (code "56") (name "unconnected-(SW-SIG1-PadD1)") (class "Default")
      (node (ref "SW-SIG1") (pin "D1") (pinfunction "D1_D1") (pintype "passive"))
    )
    (net (code "57") (name "unconnected-(SW-SIG1-PadD2)") (class "Default")
      (node (ref "SW-SIG1") (pin "D2") (pinfunction "D2_D2") (pintype "passive"))
    )
    (net (code "58") (name "unconnected-(SW-SIG1-PadD3)") (class "Default")
      (node (ref "SW-SIG1") (pin "D3") (pinfunction "D3_D3") (pintype "passive"))
    )
    (net (code "59") (name "unconnected-(SW-SIG2-PadB)") (class "Default")
      (node (ref "SW-SIG2") (pin "B") (pinfunction "B_B") (pintype "passive"))
    )
    (net (code "60") (name "unconnected-(SW-SIG2-PadB1)") (class "Default")
      (node (ref "SW-SIG2") (pin "B1") (pinfunction "B1_B1") (pintype "passive"))
    )
    (net (code "61") (name "unconnected-(SW-SIG2-PadB2)") (class "Default")
      (node (ref "SW-SIG2") (pin "B2") (pinfunction "B2_B2") (pintype "passive"))
    )
    (net (code "62") (name "unconnected-(SW-SIG2-PadB3)") (class "Default")
      (node (ref "SW-SIG2") (pin "B3") (pinfunction "B3_B3") (pintype "passive"))
    )
    (net (code "63") (name "unconnected-(SW-SIG2-PadC)") (class "Default")
      (node (ref "SW-SIG2") (pin "C") (pinfunction "C_C") (pintype "passive"))
    )
    (net (code "64") (name "unconnected-(SW-SIG2-PadC1)") (class "Default")
      (node (ref "SW-SIG2") (pin "C1") (pinfunction "C1_C1") (pintype "passive"))
    )
    (net (code "65") (name "unconnected-(SW-SIG2-PadC2)") (class "Default")
      (node (ref "SW-SIG2") (pin "C2") (pinfunction "C2_C2") (pintype "passive"))
    )
    (net (code "66") (name "unconnected-(SW-SIG2-PadC3)") (class "Default")
      (node (ref "SW-SIG2") (pin "C3") (pinfunction "C3_C3") (pintype "passive"))
    )
    (net (code "67") (name "unconnected-(SW-SIG2-PadD)") (class "Default")
      (node (ref "SW-SIG2") (pin "D") (pinfunction "D_D") (pintype "passive"))
    )
    (net (code "68") (name "unconnected-(SW-SIG2-PadD1)") (class "Default")
      (node (ref "SW-SIG2") (pin "D1") (pinfunction "D1_D1") (pintype "passive"))
    )
    (net (code "69") (name "unconnected-(SW-SIG2-PadD2)") (class "Default")
      (node (ref "SW-SIG2") (pin "D2") (pinfunction "D2_D2") (pintype "passive"))
    )
    (net (code "70") (name "unconnected-(SW-SIG2-PadD3)") (class "Default")
      (node (ref "SW-SIG2") (pin "D3") (pinfunction "D3_D3") (pintype "passive"))
    )
    (net (code "71") (name "unconnected-(SW-SW1-PadA1)") (class "Default")
      (node (ref "SW-SW1") (pin "A1") (pinfunction "A1_A1") (pintype "passive"))
    )
    (net (code "72") (name "unconnected-(SW-SW1-PadA2)") (class "Default")
      (node (ref "SW-SW1") (pin "A2") (pinfunction "A2_A2") (pintype "passive"))
    )
    (net (code "73") (name "unconnected-(SW-SW2-PadA1)") (class "Default")
      (node (ref "SW-SW2") (pin "A1") (pinfunction "A1_A1") (pintype "passive"))
    )
    (net (code "74") (name "unconnected-(SW-SW2-PadA2)") (class "Default")
      (node (ref "SW-SW2") (pin "A2") (pinfunction "A2_A2") (pintype "passive"))
    )
  )
)
